# tvbgone-2layer.net
KiCad netlist of a schematic drawn in EAGLE
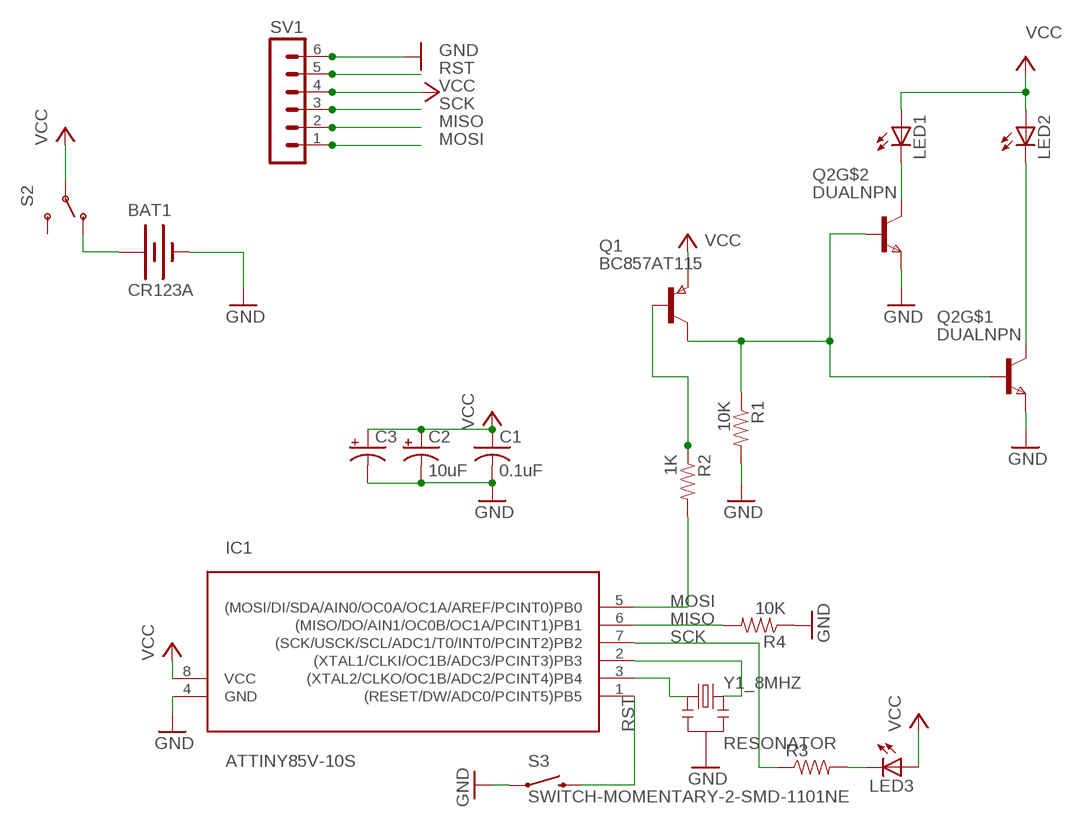
[diagram p0: schematic, sheet 1]

(export (version "E")
  (design (tool "Eeschema 10.0.6"))
  (components
    (comp (ref "BAT1")
      (value "CR123A")
      (footprint "eagle-import:TVBGONE-ADJ_BATTERY_CR123A")
      (libsource (lib "eagle-import") (part "TVBGONE-ADJ_BATTERYCR123A"))
    )
    (comp (ref "C1")
      (value "0.1uF")
      (footprint "eagle-import:C0603K")
      (libsource (lib "eagle-import") (part "C-USC0603K"))
    )
    (comp (ref "C2")
      (value "10uF")
      (footprint "eagle-import:EIA3216")
      (libsource (lib "eagle-import") (part "CAP_POL1206"))
    )
    (comp (ref "C3")
      (value "SPARKFUN_CAP_POL3528")
      (footprint "eagle-import:SPARKFUN_EIA3528")
      (libsource (lib "eagle-import") (part "SPARKFUN_CAP_POL3528"))
    )
    (comp (ref "IC1")
      (value "ATTINY85V-10S")
      (footprint "eagle-import:SOIC8")
      (libsource (lib "eagle-import") (part "ATTINY85SV-10"))
    )
    (comp (ref "LED1")
      (value "TVBGONE3_LEDSIDEIR")
      (footprint "eagle-import:TVBGONE3_SIDE_IR_NSL")
      (libsource (lib "eagle-import") (part "TVBGONE3_LEDSIDEIR"))
    )
    (comp (ref "LED2")
      (value "TVBGONE3_LEDSIDEIR")
      (footprint "eagle-import:TVBGONE3_SIDE_IR_NSL")
      (libsource (lib "eagle-import") (part "TVBGONE3_LEDSIDEIR"))
    )
    (comp (ref "LED3")
      (value "LEDCHIPLED_0603")
      (footprint "eagle-import:CHIPLED_0603")
      (libsource (lib "eagle-import") (part "LEDCHIPLED_0603"))
    )
    (comp (ref "Q1")
      (value "BC857AT115")
      (footprint "eagle-import:SOT416")
      (libsource (lib "eagle-import") (part "PNPSOT323SOT416"))
    )
    (comp (ref "Q2")
      (value "DUALNPN")
      (footprint "eagle-import:SSOT6")
      (libsource (lib "eagle-import") (part "DUALNPN"))
    )
    (comp (ref "R1")
      (value "10K")
      (footprint "eagle-import:0805")
      (libsource (lib "eagle-import") (part "RESISTOR"))
    )
    (comp (ref "R2")
      (value "1K")
      (footprint "eagle-import:0805")
      (libsource (lib "eagle-import") (part "RESISTOR"))
    )
    (comp (ref "R3")
      (value "1K")
      (footprint "eagle-import:0805")
      (libsource (lib "eagle-import") (part "RESISTOR"))
    )
    (comp (ref "R4")
      (value "10K")
      (footprint "eagle-import:0805")
      (libsource (lib "eagle-import") (part "RESISTOR"))
    )
    (comp (ref "S2")
      (value "SWITCH-SPDT-SMD-A")
      (footprint "eagle-import:SWITCH-SPST-SMD-A")
      (libsource (lib "eagle-import") (part "SWITCH-SPDT-SMD-A"))
    )
    (comp (ref "S3")
      (value "SWITCH-MOMENTARY-2-SMD-1101NE")
      (footprint "eagle-import:TACTILE-SWITCH-1101NE")
      (libsource (lib "eagle-import") (part "SWITCH-MOMENTARY-2-SMD-1101NE"))
    )
    (comp (ref "SV1")
      (value "CON-LSTB_MA06-1")
      (footprint "eagle-import:CON-LSTB_MA06-1")
      (libsource (lib "eagle-import") (part "CON-LSTB_MA06-1"))
    )
    (comp (ref "Y1_8MHZ")
      (value "RESONATOR")
      (footprint "eagle-import:SPARKFUN_RESONATOR-SMD")
      (libsource (lib "eagle-import") (part "SPARKFUN_RESONATORSMD"))
    )
  )
  (nets
    (net (code "1") (name "/MISO") (class "Default")
      (node (ref "IC1") (pin "6") (pinfunction "(MISO/DO/AIN1/OC0B/OC1A/PCINT1)PB1_6") (pintype "bidirectional"))
      (node (ref "R4") (pin "2") (pinfunction "2_2") (pintype "passive"))
      (node (ref "SV1") (pin "2") (pinfunction "2_2") (pintype "passive"))
    )
    (net (code "2") (name "/MOSI") (class "Default")
      (node (ref "IC1") (pin "5") (pinfunction "(MOSI/DI/SDA/AIN0/OC0A/OC1A/AREF/PCINT0)PB0_5") (pintype "bidirectional"))
      (node (ref "R2") (pin "2") (pinfunction "2_2") (pintype "passive"))
      (node (ref "SV1") (pin "1") (pinfunction "1_1") (pintype "passive"))
    )
    (net (code "3") (name "/RST") (class "Default")
      (node (ref "IC1") (pin "1") (pinfunction "(RESET/DW/ADC0/PCINT5)PB5_1") (pintype "bidirectional"))
      (node (ref "S3") (pin "P$2") (pinfunction "2_P$2") (pintype "passive"))
      (node (ref "SV1") (pin "5") (pinfunction "5_5") (pintype "passive"))
    )
    (net (code "4") (name "/SCK") (class "Default")
      (node (ref "IC1") (pin "7") (pinfunction "(SCK/USCK/SCL/ADC1/T0/INT0/PCINT2)PB2_7") (pintype "bidirectional"))
      (node (ref "R3") (pin "1") (pinfunction "1_1") (pintype "passive"))
      (node (ref "SV1") (pin "3") (pinfunction "3_3") (pintype "passive"))
    )
    (net (code "5") (name "GND") (class "Default")
      (node (ref "BAT1") (pin "-") (pinfunction "-_-") (pintype "power_in"))
      (node (ref "C1") (pin "2") (pinfunction "2_2") (pintype "passive"))
      (node (ref "C2") (pin "C") (pinfunction "-_C") (pintype "passive"))
      (node (ref "C3") (pin "C") (pinfunction "-_C") (pintype "passive"))
      (node (ref "IC1") (pin "4") (pinfunction "GND_4") (pintype "bidirectional"))
      (node (ref "Q2") (pin "2") (pinfunction "E_2") (pintype "passive"))
      (node (ref "Q2") (pin "5") (pinfunction "E_5") (pintype "passive"))
      (node (ref "R1") (pin "2") (pinfunction "2_2") (pintype "passive"))
      (node (ref "R4") (pin "1") (pinfunction "1_1") (pintype "passive"))
      (node (ref "S3") (pin "P$1") (pinfunction "1_P$1") (pintype "passive"))
      (node (ref "SV1") (pin "6") (pinfunction "6_6") (pintype "passive"))
      (node (ref "Y1_8MHZ") (pin "2") (pinfunction "2_2") (pintype "passive"))
    )
    (net (code "6") (name "Net-(IC1-(XTAL1{slash}CLKI{slash}OC1B{slash}ADC3{slash}PCINT3)PB3)") (class "Default")
      (node (ref "IC1") (pin "2") (pinfunction "(XTAL1/CLKI/OC1B/ADC3/PCINT3)PB3_2") (pintype "bidirectional"))
      (node (ref "Y1_8MHZ") (pin "3") (pinfunction "3_3") (pintype "passive"))
    )
    (net (code "7") (name "Net-(IC1-(XTAL2{slash}CLKO{slash}OC1B{slash}ADC2{slash}PCINT4)PB4)") (class "Default")
      (node (ref "IC1") (pin "3") (pinfunction "(XTAL2/CLKO/OC1B/ADC2/PCINT4)PB4_3") (pintype "bidirectional"))
      (node (ref "Y1_8MHZ") (pin "1") (pinfunction "1_1") (pintype "passive"))
    )
    (net (code "8") (name "Net-(LED3-PadC)") (class "Default")
      (node (ref "LED3") (pin "C") (pinfunction "C_C") (pintype "passive"))
      (node (ref "R3") (pin "2") (pinfunction "2_2") (pintype "passive"))
    )
    (net (code "9") (name "Net-(Q1-B)") (class "Default")
      (node (ref "Q1") (pin "2") (pinfunction "B_2") (pintype "passive"))
      (node (ref "R2") (pin "1") (pinfunction "1_1") (pintype "passive"))
    )
    (net (code "10") (name "Net-(Q1-C)") (class "Default")
      (node (ref "Q1") (pin "1") (pinfunction "C_1") (pintype "passive"))
      (node (ref "Q2") (pin "1") (pinfunction "B_1") (pintype "passive"))
      (node (ref "Q2") (pin "3") (pinfunction "B_3") (pintype "passive"))
      (node (ref "R1") (pin "1") (pinfunction "1_1") (pintype "passive"))
    )
    (net (code "11") (name "Net-(Q2A-C)") (class "Default")
      (node (ref "LED2") (pin "C") (pinfunction "C_C") (pintype "passive"))
      (node (ref "Q2") (pin "6") (pinfunction "C_6") (pintype "passive"))
    )
    (net (code "12") (name "Net-(Q2B-C)") (class "Default")
      (node (ref "LED1") (pin "C") (pinfunction "C_C") (pintype "passive"))
      (node (ref "Q2") (pin "4") (pinfunction "C_4") (pintype "passive"))
    )
    (net (code "13") (name "Net-(S2-O)") (class "Default")
      (node (ref "BAT1") (pin "+") (pinfunction "+_+") (pintype "power_in"))
      (node (ref "S2") (pin "1") (pinfunction "O_1") (pintype "passive"))
    )
    (net (code "14") (name "VCC") (class "Default")
      (node (ref "C1") (pin "1") (pinfunction "1_1") (pintype "passive"))
      (node (ref "C2") (pin "A") (pinfunction "+_A") (pintype "passive"))
      (node (ref "C3") (pin "A") (pinfunction "+_A") (pintype "passive"))
      (node (ref "IC1") (pin "8") (pinfunction "VCC_8") (pintype "bidirectional"))
      (node (ref "LED1") (pin "A") (pinfunction "A_A") (pintype "passive"))
      (node (ref "LED2") (pin "A") (pinfunction "A_A") (pintype "passive"))
      (node (ref "LED3") (pin "A") (pinfunction "A_A") (pintype "passive"))
      (node (ref "Q1") (pin "3") (pinfunction "E_3") (pintype "passive"))
      (node (ref "S2") (pin "2") (pinfunction "P_2") (pintype "passive"))
      (node (ref "SV1") (pin "4") (pinfunction "4_4") (pintype "passive"))
    )
    (net (code "15") (name "unconnected-(S2-S-Pad3)") (class "Default")
      (node (ref "S2") (pin "3") (pinfunction "S_3") (pintype "passive"))
    )
  )
)
